# 4915.net
KiCad netlist of a schematic drawn in EAGLE
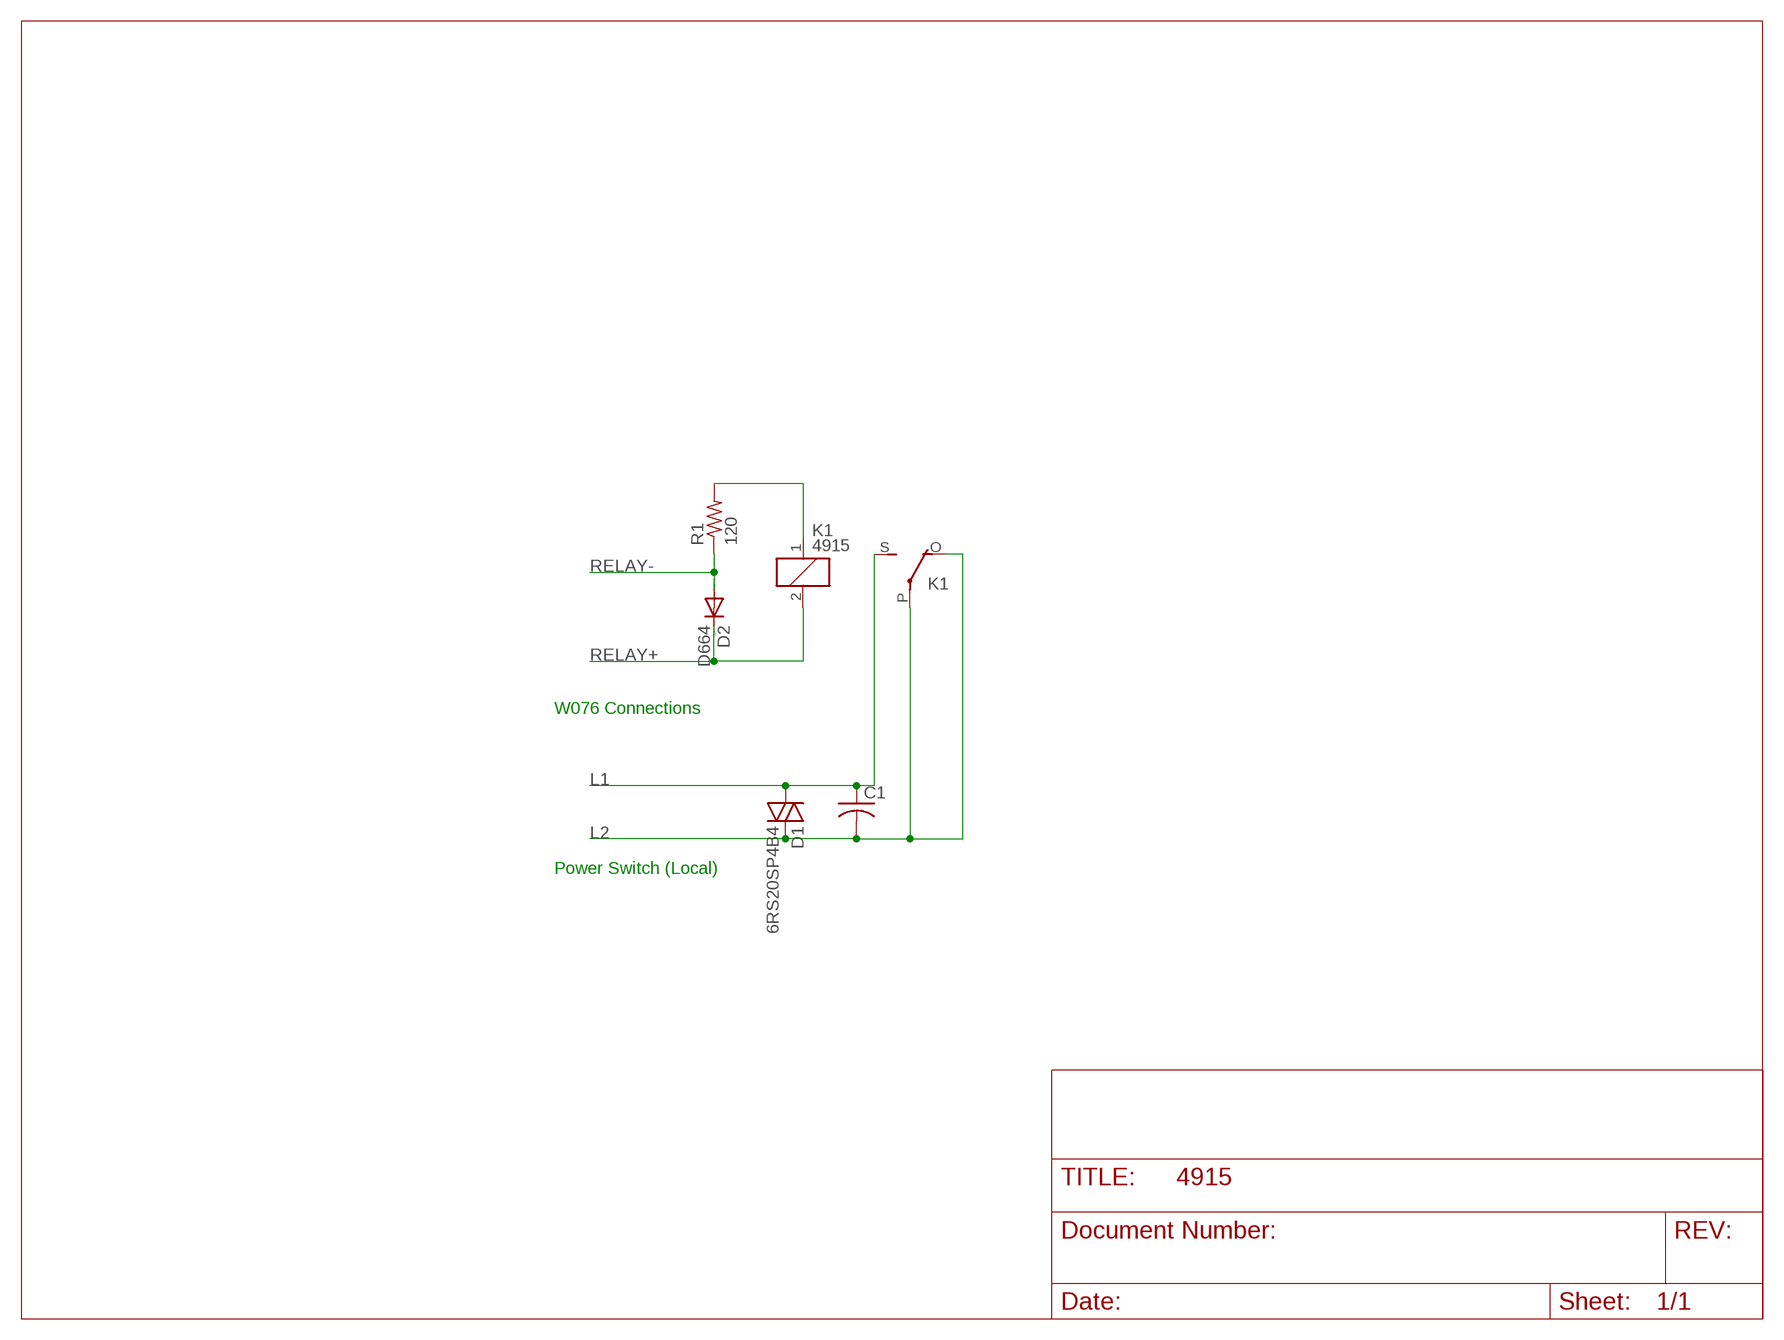
[diagram p0: schematic, sheet 1]

(export (version "E")
  (design (tool "Eeschema 10.0.6"))
  (components
    (comp (ref "C1")
      (value "C-US050-025X075")
      (footprint "eagle-import:C050-025X075")
      (libsource (lib "eagle-import") (part "C-US050-025X075"))
    )
    (comp (ref "D1")
      (value "6RS20SP4B4")
      (footprint "eagle-import:GT32")
      (libsource (lib "eagle-import") (part "DIAC-GT32"))
    )
    (comp (ref "D2")
      (value "D664")
      (footprint "eagle-import:DO35-10")
      (libsource (lib "eagle-import") (part "1N4148DO35-10"))
    )
    (comp (ref "K1")
      (value "4915")
      (footprint "eagle-import:G6RW")
      (libsource (lib "eagle-import") (part "G6RW"))
    )
    (comp (ref "R1")
      (value "120")
      (footprint "eagle-import:0207_10")
      (libsource (lib "eagle-import") (part "R-US_0207/10"))
    )
  )
  (nets
    (net (code "1") (name "/L1") (class "Default")
      (node (ref "C1") (pin "1") (pinfunction "1_1") (pintype "passive"))
      (node (ref "D1") (pin "1") (pinfunction "1_1") (pintype "passive"))
      (node (ref "K1") (pin "S") (pinfunction "S_S") (pintype "passive"))
    )
    (net (code "2") (name "/L2") (class "Default")
      (node (ref "C1") (pin "2") (pinfunction "2_2") (pintype "passive"))
      (node (ref "D1") (pin "2") (pinfunction "2_2") (pintype "passive"))
      (node (ref "K1") (pin "O") (pinfunction "O_O") (pintype "passive"))
      (node (ref "K1") (pin "P") (pinfunction "P_P") (pintype "passive"))
    )
    (net (code "3") (name "/RELAY+") (class "Default")
      (node (ref "D2") (pin "C") (pinfunction "C_C") (pintype "passive"))
      (node (ref "K1") (pin "2") (pinfunction "2_2") (pintype "passive"))
    )
    (net (code "4") (name "/RELAY-") (class "Default")
      (node (ref "D2") (pin "A") (pinfunction "A_A") (pintype "passive"))
      (node (ref "R1") (pin "1") (pinfunction "1_1") (pintype "passive"))
    )
    (net (code "5") (name "Net-(K1-Pad1)") (class "Default")
      (node (ref "K1") (pin "1") (pinfunction "1_1") (pintype "passive"))
      (node (ref "R1") (pin "2") (pinfunction "2_2") (pintype "passive"))
    )
  )
)
